# Buck_Converter_AX3116.net
KiCad netlist of a schematic drawn in Altium Designer
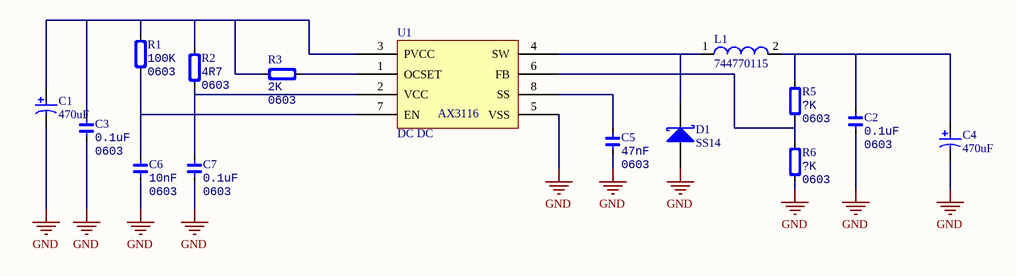
[diagram p0: Buck Converter_AX3116.SchDoc]

(export (version "E")
  (design (tool "Eeschema 10.0.6"))
  (components
    (comp (ref "C1")
      (value "470uF")
      (footprint "NIC-CAPA2-10X10_V")
      (fields (field (name "PARTNUMBER") "UUD1E471MNL1GS") (field (name "MANUFACTURER") "Nichicon"))
      (libsource (lib "Altium Content Vault") (part "NIC-CAP-P-2"))
    )
    (comp (ref "C2")
      (value "0.1uF")
      (footprint "CAP_0603")
      (description "Capacitor")
      (fields (field (name "TYPE") "0603") (field (name "Comment") "C0603"))
      (libsource (lib "Capacitors") (part "Cap_0603"))
    )
    (comp (ref "C3")
      (value "0.1uF")
      (footprint "CAP_0603")
      (description "Capacitor")
      (fields (field (name "TYPE") "0603") (field (name "Comment") "C0603"))
      (libsource (lib "Capacitors") (part "Cap_0603"))
    )
    (comp (ref "C4")
      (value "470uF")
      (footprint "NIC-CAPA2-10X10_V")
      (fields (field (name "PARTNUMBER") "UUD1E471MNL1GS") (field (name "MANUFACTURER") "Nichicon"))
      (libsource (lib "Altium Content Vault") (part "NIC-CAP-P-2"))
    )
    (comp (ref "C5")
      (value "47nF")
      (footprint "CAP_0603")
      (description "Capacitor")
      (fields (field (name "TYPE") "0603") (field (name "Comment") "C0603"))
      (libsource (lib "Capacitors") (part "Cap_0603"))
    )
    (comp (ref "C6")
      (value "10nF")
      (footprint "CAP_0603")
      (description "Capacitor")
      (fields (field (name "TYPE") "0603") (field (name "Comment") "C0603"))
      (libsource (lib "Capacitors") (part "Cap_0603"))
    )
    (comp (ref "C7")
      (value "0.1uF")
      (footprint "CAP_0603")
      (description "Capacitor")
      (fields (field (name "TYPE") "0603") (field (name "Comment") "C0603"))
      (libsource (lib "Capacitors") (part "Cap_0603"))
    )
    (comp (ref "D1") (value "SS14") (footprint "SMA") (libsource (lib "Diodes") (part "Diode Schottky")))
    (comp (ref "L1")
      (value "744770115")
      (footprint "WE-PD-XL")
      (description "SMD-Shielded Power Inductor WE-PD, L = 15.0 µH")
      (libsource (lib "Altium Content Vault") (part "PAS-IND-INDUCTOR-2"))
    )
    (comp (ref "R1")
      (value "100K")
      (footprint "RES_0603")
      (description "Resistor")
      (fields (field (name "TYPE") "0603") (field (name "Comment") "R0603"))
      (libsource (lib "Resistors") (part "Res_0603"))
    )
    (comp (ref "R2")
      (value "4R7")
      (footprint "RES_0603")
      (description "Resistor")
      (fields (field (name "TYPE") "0603") (field (name "Comment") "R0603"))
      (libsource (lib "Resistors") (part "Res_0603"))
    )
    (comp (ref "R3")
      (value "2K")
      (footprint "RES_0603")
      (description "Resistor")
      (fields (field (name "TYPE") "0603") (field (name "Comment") "R0603"))
      (libsource (lib "Resistors") (part "Res_0603"))
    )
    (comp (ref "R5")
      (value "?K")
      (footprint "RES_0603")
      (description "Resistor")
      (fields (field (name "TYPE") "0603") (field (name "Comment") "R0603"))
      (libsource (lib "Resistors") (part "Res_0603"))
    )
    (comp (ref "R6")
      (value "?K")
      (footprint "RES_0603")
      (description "Resistor")
      (fields (field (name "TYPE") "0603") (field (name "Comment") "R0603"))
      (libsource (lib "Resistors") (part "Res_0603"))
    )
    (comp (ref "U1") (value "DC DC") (footprint "SOP-8L-EP") (libsource (lib "IC") (part "AX3116")))
  )
  (nets
    (net (code "1") (name "GND") (class "Default")
      (node (ref "C1") (pin "2") (pinfunction "2_2") (pintype "passive"))
      (node (ref "C2") (pin "1") (pinfunction "1_1") (pintype "passive"))
      (node (ref "C3") (pin "1") (pinfunction "1_1") (pintype "passive"))
      (node (ref "C4") (pin "2") (pinfunction "2_2") (pintype "passive"))
      (node (ref "C5") (pin "1") (pinfunction "1_1") (pintype "passive"))
      (node (ref "C6") (pin "1") (pinfunction "1_1") (pintype "passive"))
      (node (ref "C7") (pin "1") (pinfunction "1_1") (pintype "passive"))
      (node (ref "D1") (pin "A") (pinfunction "A_A") (pintype "passive"))
      (node (ref "R6") (pin "1") (pinfunction "1_1") (pintype "passive"))
      (node (ref "U1") (pin "5") (pinfunction "VSS_5") (pintype "passive"))
    )
    (net (code "2") (name "Net-(C2-Pad2)") (class "Default")
      (node (ref "C2") (pin "2") (pinfunction "2_2") (pintype "passive"))
      (node (ref "C4") (pin "1") (pinfunction "1_1") (pintype "passive"))
      (node (ref "L1") (pin "2") (pinfunction "2_2") (pintype "passive"))
      (node (ref "R5") (pin "2") (pinfunction "2_2") (pintype "passive"))
    )
    (net (code "3") (name "Net-(U1-EN)") (class "Default")
      (node (ref "C6") (pin "2") (pinfunction "2_2") (pintype "passive"))
      (node (ref "R1") (pin "1") (pinfunction "1_1") (pintype "passive"))
      (node (ref "U1") (pin "7") (pinfunction "EN_7") (pintype "passive"))
    )
    (net (code "4") (name "Net-(U1-FB)") (class "Default")
      (node (ref "R5") (pin "1") (pinfunction "1_1") (pintype "passive"))
      (node (ref "R6") (pin "2") (pinfunction "2_2") (pintype "passive"))
      (node (ref "U1") (pin "6") (pinfunction "FB_6") (pintype "passive"))
    )
    (net (code "5") (name "Net-(U1-OCSET)") (class "Default")
      (node (ref "R3") (pin "2") (pinfunction "2_2") (pintype "passive"))
      (node (ref "U1") (pin "1") (pinfunction "OCSET_1") (pintype "passive"))
    )
    (net (code "6") (name "Net-(U1-PVCC)") (class "Default")
      (node (ref "C1") (pin "1") (pinfunction "1_1") (pintype "passive"))
      (node (ref "C3") (pin "2") (pinfunction "2_2") (pintype "passive"))
      (node (ref "R1") (pin "2") (pinfunction "2_2") (pintype "passive"))
      (node (ref "R2") (pin "2") (pinfunction "2_2") (pintype "passive"))
      (node (ref "R3") (pin "1") (pinfunction "1_1") (pintype "passive"))
      (node (ref "U1") (pin "3") (pinfunction "PVCC_3") (pintype "passive"))
    )
    (net (code "7") (name "Net-(U1-SS)") (class "Default")
      (node (ref "C5") (pin "2") (pinfunction "2_2") (pintype "passive"))
      (node (ref "U1") (pin "8") (pinfunction "SS_8") (pintype "passive"))
    )
    (net (code "8") (name "Net-(U1-SW)") (class "Default")
      (node (ref "D1") (pin "K") (pinfunction "K_K") (pintype "passive"))
      (node (ref "L1") (pin "1") (pinfunction "1_1") (pintype "passive"))
      (node (ref "U1") (pin "4") (pinfunction "SW_4") (pintype "passive"))
    )
    (net (code "9") (name "Net-(U1-VCC)") (class "Default")
      (node (ref "C7") (pin "2") (pinfunction "2_2") (pintype "passive"))
      (node (ref "R2") (pin "1") (pinfunction "1_1") (pintype "passive"))
      (node (ref "U1") (pin "2") (pinfunction "VCC_2") (pintype "passive"))
    )
  )
)
